# Solar_battery.net
KiCad netlist of a schematic drawn in EAGLE
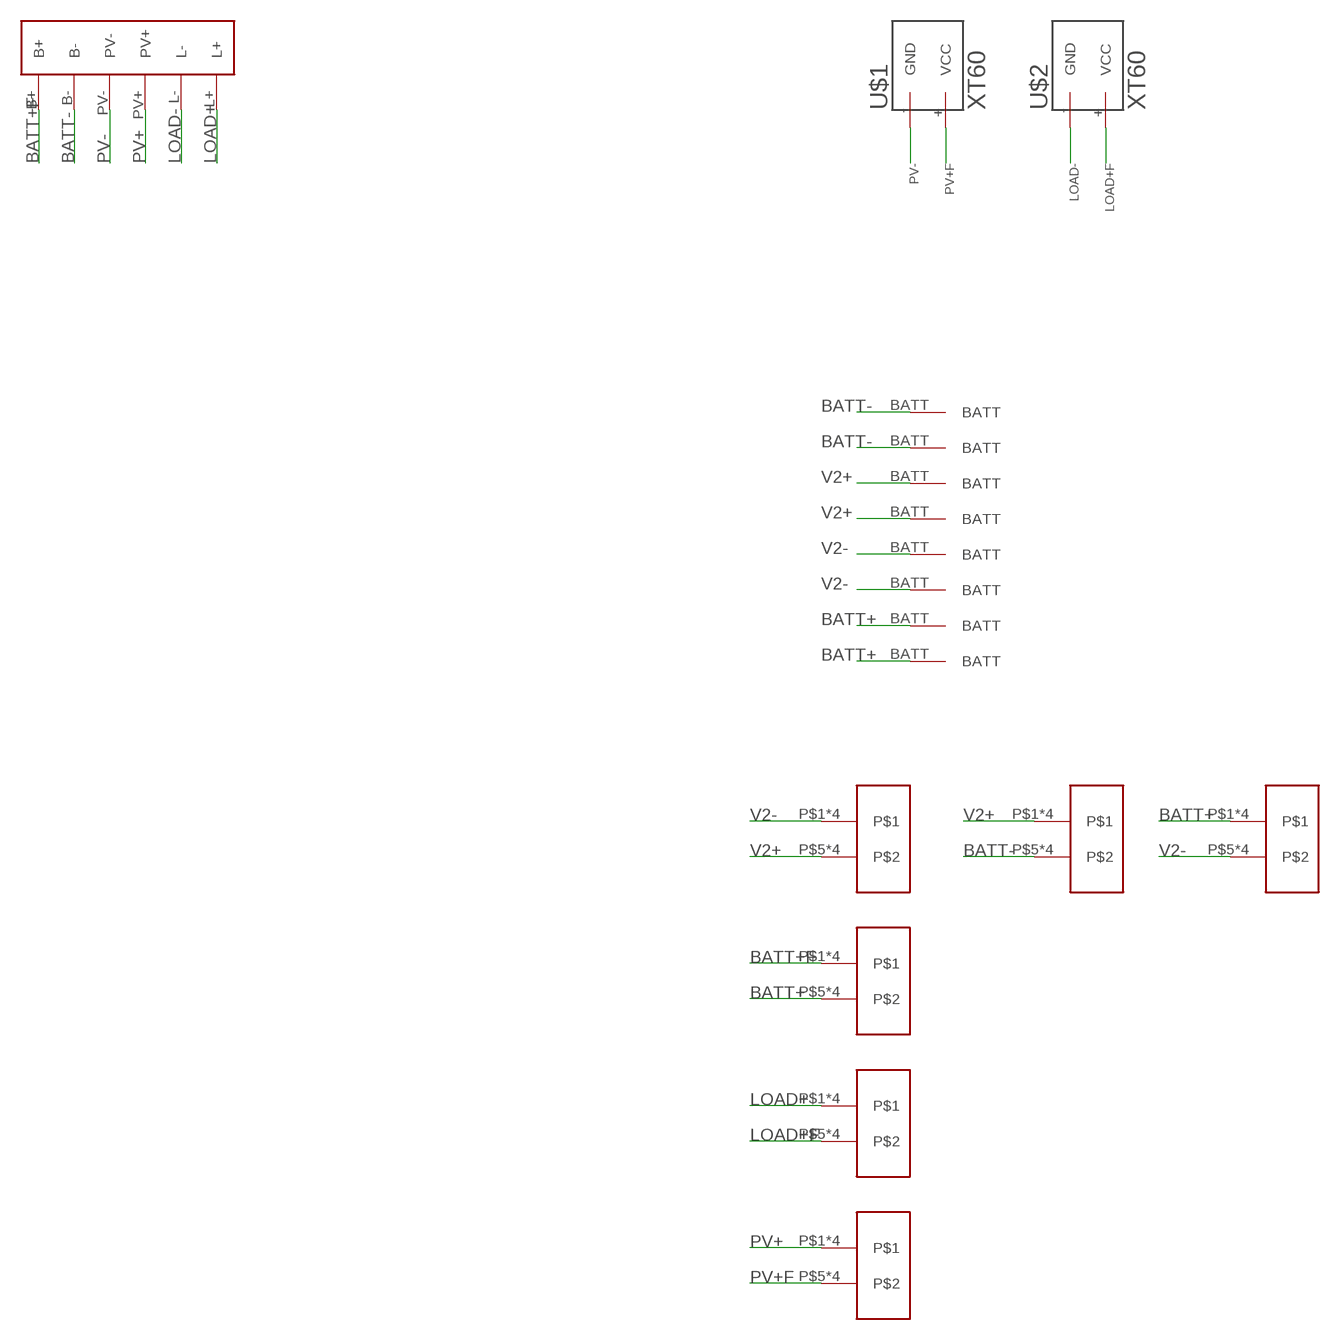
[diagram p0: schematic, sheet 1]

(export (version "E")
  (design (tool "Eeschema 10.0.6"))
  (components
    (comp (ref "U$1")
      (value "XT60")
      (footprint "eagle-import:XT60")
      (libsource (lib "eagle-import") (part "XT60"))
    )
    (comp (ref "U$2")
      (value "XT60")
      (footprint "eagle-import:XT60")
      (libsource (lib "eagle-import") (part "XT60"))
    )
    (comp (ref "U$3")
      (value "C40_40135")
      (footprint "eagle-import:C40_40135")
      (libsource (lib "eagle-import") (part "C40_40135"))
    )
    (comp (ref "U$4")
      (value "C40_40135")
      (footprint "eagle-import:C40_40135")
      (libsource (lib "eagle-import") (part "C40_40135"))
    )
    (comp (ref "U$5")
      (value "C40_40135")
      (footprint "eagle-import:C40_40135")
      (libsource (lib "eagle-import") (part "C40_40135"))
    )
    (comp (ref "U$6")
      (value "C40_40135")
      (footprint "eagle-import:C40_40135")
      (libsource (lib "eagle-import") (part "C40_40135"))
    )
    (comp (ref "U$7")
      (value "C40_40135")
      (footprint "eagle-import:C40_40135")
      (libsource (lib "eagle-import") (part "C40_40135"))
    )
    (comp (ref "U$8")
      (value "C40_40135")
      (footprint "eagle-import:C40_40135")
      (libsource (lib "eagle-import") (part "C40_40135"))
    )
    (comp (ref "U$9")
      (value "C40_40135")
      (footprint "eagle-import:C40_40135")
      (libsource (lib "eagle-import") (part "C40_40135"))
    )
    (comp (ref "U$10")
      (value "C40_40135")
      (footprint "eagle-import:C40_40135")
      (libsource (lib "eagle-import") (part "C40_40135"))
    )
    (comp (ref "U$11")
      (value "FUSEHOLDER_178.6164")
      (footprint "eagle-import:FUSEHOLDER_178.6164")
      (libsource (lib "eagle-import") (part "FUSEHOLDER_178.6164"))
    )
    (comp (ref "U$12")
      (value "FUSEHOLDER_178.6164")
      (footprint "eagle-import:FUSEHOLDER_178.6164")
      (libsource (lib "eagle-import") (part "FUSEHOLDER_178.6164"))
    )
    (comp (ref "U$13")
      (value "FUSEHOLDER_178.6164")
      (footprint "eagle-import:FUSEHOLDER_178.6164")
      (libsource (lib "eagle-import") (part "FUSEHOLDER_178.6164"))
    )
    (comp (ref "U$14")
      (value "FUSEHOLDER_178.6164")
      (footprint "eagle-import:FUSEHOLDER_178.6164")
      (libsource (lib "eagle-import") (part "FUSEHOLDER_178.6164"))
    )
    (comp (ref "U$15")
      (value "FUSEHOLDER_178.6164")
      (footprint "eagle-import:FUSEHOLDER_178.6164")
      (libsource (lib "eagle-import") (part "FUSEHOLDER_178.6164"))
    )
    (comp (ref "U$16")
      (value "FUSEHOLDER_178.6164")
      (footprint "eagle-import:FUSEHOLDER_178.6164")
      (libsource (lib "eagle-import") (part "FUSEHOLDER_178.6164"))
    )
    (comp (ref "U$17")
      (value "SMARTSOLAR_75/15")
      (footprint "eagle-import:SMARTSOLAR_75_15")
      (libsource (lib "eagle-import") (part "SMARTSOLAR_75/15"))
    )
  )
  (nets
    (net (code "1") (name "/BATT+") (class "Default")
      (node (ref "U$10") (pin "BATT") (pinfunction "BATT_BATT") (pintype "bidirectional"))
      (node (ref "U$12") (pin "P$5") (pinfunction "P$2_P$5") (pintype "bidirectional"))
      (node (ref "U$12") (pin "P$6") (pinfunction "P$2_P$6") (pintype "bidirectional"))
      (node (ref "U$12") (pin "P$7") (pinfunction "P$2_P$7") (pintype "bidirectional"))
      (node (ref "U$12") (pin "P$8") (pinfunction "P$2_P$8") (pintype "bidirectional"))
      (node (ref "U$16") (pin "P$1") (pinfunction "P$1_P$1") (pintype "bidirectional"))
      (node (ref "U$16") (pin "P$2") (pinfunction "P$1_P$2") (pintype "bidirectional"))
      (node (ref "U$16") (pin "P$3") (pinfunction "P$1_P$3") (pintype "bidirectional"))
      (node (ref "U$16") (pin "P$4") (pinfunction "P$1_P$4") (pintype "bidirectional"))
      (node (ref "U$9") (pin "BATT") (pinfunction "BATT_BATT") (pintype "bidirectional"))
    )
    (net (code "2") (name "/BATT+F") (class "Default")
      (node (ref "U$12") (pin "P$1") (pinfunction "P$1_P$1") (pintype "bidirectional"))
      (node (ref "U$12") (pin "P$2") (pinfunction "P$1_P$2") (pintype "bidirectional"))
      (node (ref "U$12") (pin "P$3") (pinfunction "P$1_P$3") (pintype "bidirectional"))
      (node (ref "U$12") (pin "P$4") (pinfunction "P$1_P$4") (pintype "bidirectional"))
      (node (ref "U$17") (pin "B+") (pinfunction "B+_B+") (pintype "bidirectional"))
    )
    (net (code "3") (name "/BATT-") (class "Default")
      (node (ref "U$15") (pin "P$5") (pinfunction "P$2_P$5") (pintype "bidirectional"))
      (node (ref "U$15") (pin "P$6") (pinfunction "P$2_P$6") (pintype "bidirectional"))
      (node (ref "U$15") (pin "P$7") (pinfunction "P$2_P$7") (pintype "bidirectional"))
      (node (ref "U$15") (pin "P$8") (pinfunction "P$2_P$8") (pintype "bidirectional"))
      (node (ref "U$17") (pin "B-") (pinfunction "B-_B-") (pintype "bidirectional"))
      (node (ref "U$3") (pin "BATT") (pinfunction "BATT_BATT") (pintype "bidirectional"))
      (node (ref "U$4") (pin "BATT") (pinfunction "BATT_BATT") (pintype "bidirectional"))
    )
    (net (code "4") (name "/LOAD+") (class "Default")
      (node (ref "U$13") (pin "P$1") (pinfunction "P$1_P$1") (pintype "bidirectional"))
      (node (ref "U$13") (pin "P$2") (pinfunction "P$1_P$2") (pintype "bidirectional"))
      (node (ref "U$13") (pin "P$3") (pinfunction "P$1_P$3") (pintype "bidirectional"))
      (node (ref "U$13") (pin "P$4") (pinfunction "P$1_P$4") (pintype "bidirectional"))
      (node (ref "U$17") (pin "L+") (pinfunction "L+_L+") (pintype "bidirectional"))
    )
    (net (code "5") (name "/PV+") (class "Default")
      (node (ref "U$14") (pin "P$1") (pinfunction "P$1_P$1") (pintype "bidirectional"))
      (node (ref "U$14") (pin "P$2") (pinfunction "P$1_P$2") (pintype "bidirectional"))
      (node (ref "U$14") (pin "P$3") (pinfunction "P$1_P$3") (pintype "bidirectional"))
      (node (ref "U$14") (pin "P$4") (pinfunction "P$1_P$4") (pintype "bidirectional"))
      (node (ref "U$17") (pin "PV+") (pinfunction "PV+_PV+") (pintype "bidirectional"))
    )
    (net (code "6") (name "/V2+") (class "Default")
      (node (ref "U$11") (pin "P$5") (pinfunction "P$2_P$5") (pintype "bidirectional"))
      (node (ref "U$11") (pin "P$6") (pinfunction "P$2_P$6") (pintype "bidirectional"))
      (node (ref "U$11") (pin "P$7") (pinfunction "P$2_P$7") (pintype "bidirectional"))
      (node (ref "U$11") (pin "P$8") (pinfunction "P$2_P$8") (pintype "bidirectional"))
      (node (ref "U$15") (pin "P$1") (pinfunction "P$1_P$1") (pintype "bidirectional"))
      (node (ref "U$15") (pin "P$2") (pinfunction "P$1_P$2") (pintype "bidirectional"))
      (node (ref "U$15") (pin "P$3") (pinfunction "P$1_P$3") (pintype "bidirectional"))
      (node (ref "U$15") (pin "P$4") (pinfunction "P$1_P$4") (pintype "bidirectional"))
      (node (ref "U$5") (pin "BATT") (pinfunction "BATT_BATT") (pintype "bidirectional"))
      (node (ref "U$6") (pin "BATT") (pinfunction "BATT_BATT") (pintype "bidirectional"))
    )
    (net (code "7") (name "/V2-") (class "Default")
      (node (ref "U$11") (pin "P$1") (pinfunction "P$1_P$1") (pintype "bidirectional"))
      (node (ref "U$11") (pin "P$2") (pinfunction "P$1_P$2") (pintype "bidirectional"))
      (node (ref "U$11") (pin "P$3") (pinfunction "P$1_P$3") (pintype "bidirectional"))
      (node (ref "U$11") (pin "P$4") (pinfunction "P$1_P$4") (pintype "bidirectional"))
      (node (ref "U$16") (pin "P$5") (pinfunction "P$2_P$5") (pintype "bidirectional"))
      (node (ref "U$16") (pin "P$6") (pinfunction "P$2_P$6") (pintype "bidirectional"))
      (node (ref "U$16") (pin "P$7") (pinfunction "P$2_P$7") (pintype "bidirectional"))
      (node (ref "U$16") (pin "P$8") (pinfunction "P$2_P$8") (pintype "bidirectional"))
      (node (ref "U$7") (pin "BATT") (pinfunction "BATT_BATT") (pintype "bidirectional"))
      (node (ref "U$8") (pin "BATT") (pinfunction "BATT_BATT") (pintype "bidirectional"))
    )
    (net (code "8") (name "LOAD+F") (class "Default")
      (node (ref "U$13") (pin "P$5") (pinfunction "P$2_P$5") (pintype "bidirectional"))
      (node (ref "U$13") (pin "P$6") (pinfunction "P$2_P$6") (pintype "bidirectional"))
      (node (ref "U$13") (pin "P$7") (pinfunction "P$2_P$7") (pintype "bidirectional"))
      (node (ref "U$13") (pin "P$8") (pinfunction "P$2_P$8") (pintype "bidirectional"))
      (node (ref "U$2") (pin "+") (pinfunction "VCC_+") (pintype "bidirectional"))
    )
    (net (code "9") (name "LOAD-") (class "Default")
      (node (ref "U$17") (pin "L-") (pinfunction "L-_L-") (pintype "bidirectional"))
      (node (ref "U$2") (pin "-") (pinfunction "GND_-") (pintype "bidirectional"))
    )
    (net (code "10") (name "PV+F") (class "Default")
      (node (ref "U$1") (pin "+") (pinfunction "VCC_+") (pintype "bidirectional"))
      (node (ref "U$14") (pin "P$5") (pinfunction "P$2_P$5") (pintype "bidirectional"))
      (node (ref "U$14") (pin "P$6") (pinfunction "P$2_P$6") (pintype "bidirectional"))
      (node (ref "U$14") (pin "P$7") (pinfunction "P$2_P$7") (pintype "bidirectional"))
      (node (ref "U$14") (pin "P$8") (pinfunction "P$2_P$8") (pintype "bidirectional"))
    )
    (net (code "11") (name "PV-") (class "Default")
      (node (ref "U$1") (pin "-") (pinfunction "GND_-") (pintype "bidirectional"))
      (node (ref "U$17") (pin "PV-") (pinfunction "PV-_PV-") (pintype "bidirectional"))
    )
  )
)
